# 7_dc_dc_3V3_3V3_Deployment_ANT.net
KiCad netlist of a schematic drawn in Altium Designer
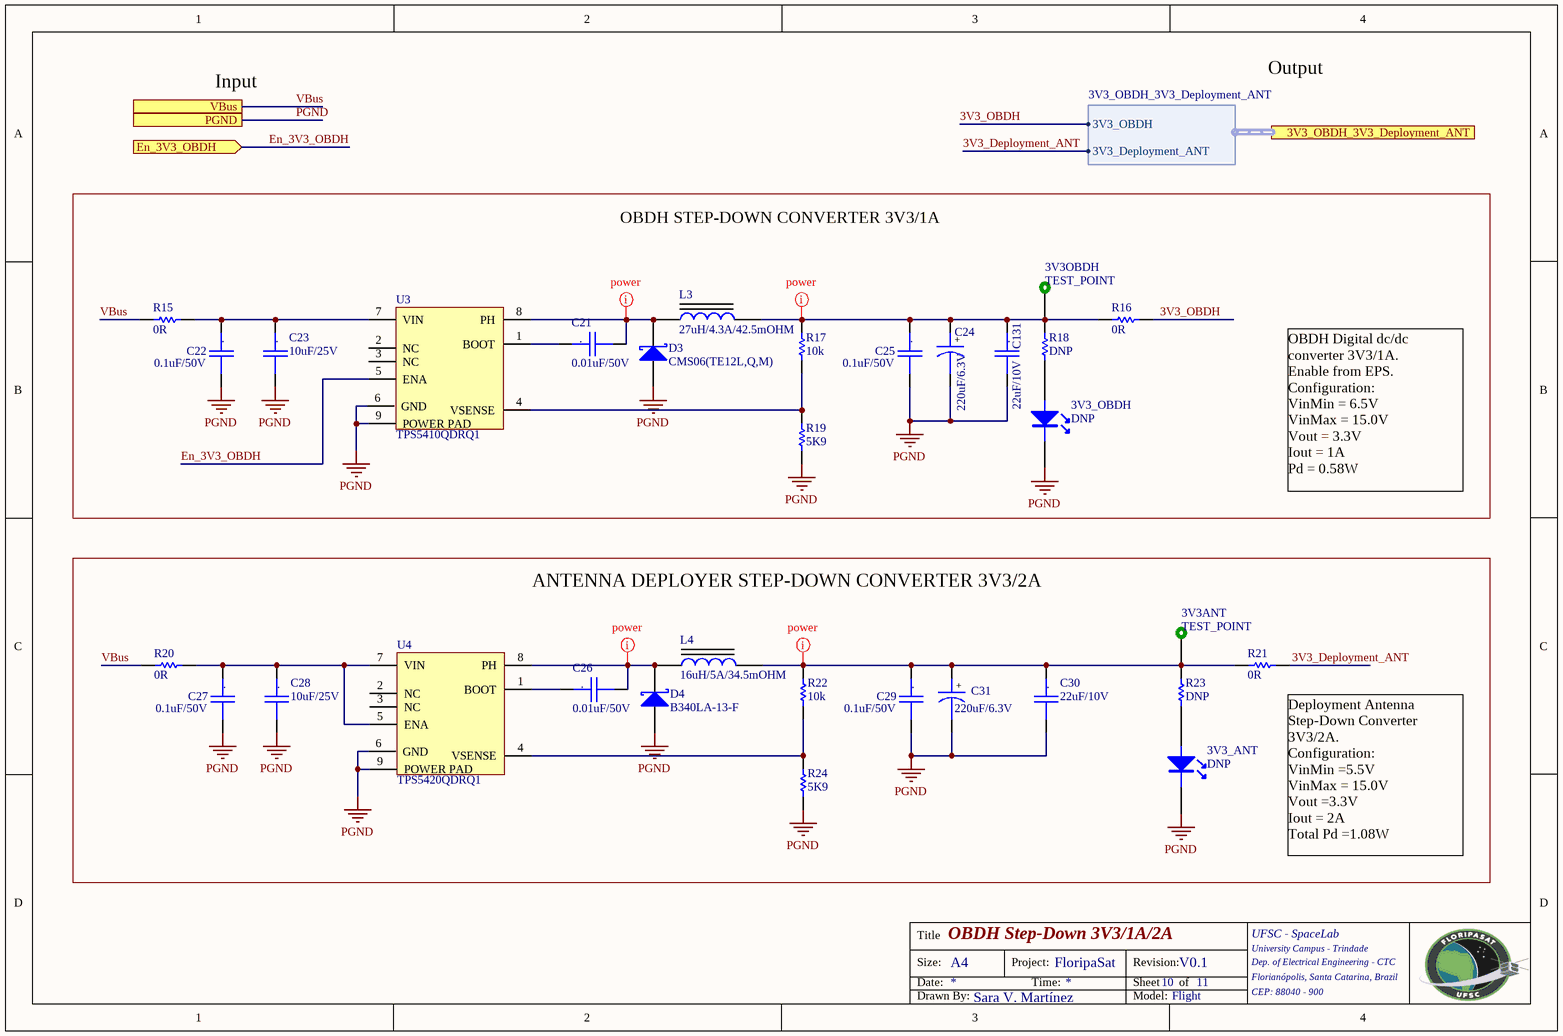
[diagram p0: 7_dc_dc_3V3_3V3_Deployment_ANT.SchDoc]

(export (version "E")
  (design (tool "Eeschema 10.0.6"))
  (components
    (comp (ref "3V3ANT")
      (value "TEST_POINT")
      (footprint "TEST_POINT")
      (description "Test point")
      (libsource (lib "Floripasat_lib") (part "TEST_POINT"))
    )
    (comp (ref "3V3OBDH")
      (value "TEST_POINT")
      (footprint "TEST_POINT")
      (description "Test point")
      (libsource (lib "Floripasat_lib") (part "TEST_POINT"))
    )
    (comp (ref "3V3_ANT")
      (value "DNP")
      (footprint "0603-LED")
      (description "SMD Green LED")
      (fields (field (name "PARTNUMBER") "150060VS75000"))
      (libsource (lib "FloripaSatSchlib") (part "LED/G_0603"))
    )
    (comp (ref "3V3_OBDH")
      (value "DNP")
      (footprint "0603-LED")
      (description "SMD Green LED")
      (fields (field (name "PARTNUMBER") "150060VS75000"))
      (libsource (lib "FloripaSatSchlib") (part "LED/G_0603"))
    )
    (comp (ref "C21")
      (value "0.01uF/50V")
      (footprint "CC0805")
      (description "CAP CER 0.01uF 50V 10% X7R 0805")
      (fields (field (name "PARTNUMBER") "08055C103KAT4A"))
      (libsource (lib "PCB_Project_FlightModel_EPS") (part "Cap_Cer_X7R_0.01uF_50V_0805"))
    )
    (comp (ref "C22")
      (value "0.1uF/50V")
      (footprint "CC0805")
      (description "CAP CER 0.1UF 50V 10% X7R 0805")
      (fields (field (name "PARTNUMBER") "CC0805KRX7R9BB104"))
      (libsource (lib "PCB_Project_FlightModel_EPS") (part "Cap_Cer_X7R_0.1uF_50V_0805"))
    )
    (comp (ref "C23")
      (value "10uF/25V")
      (footprint "CC1206")
      (description "CAP CER 10uF 25V 10% X7R 1206")
      (fields (field (name "PARTNUMBER") "GRM31CR71E106KA12L"))
      (libsource (lib "Floripasat_lib") (part "Cap_Cer_X7R_10uF_25V_1206"))
    )
    (comp (ref "C24")
      (value "220uF/6.3V")
      (footprint "FloripaSatPcbLib:cc1210")
      (description "CAP Tantalum 220uF 6.3V 20% 1210")
      (fields (field (name "PARTNUMBER") "6TPE220MAZB"))
      (libsource (lib "Floripasat_lib") (part "Cap_Tant_SMD_220uF_6.3V_1210"))
    )
    (comp (ref "C25")
      (value "0.1uF/50V")
      (footprint "CC0805")
      (description "CAP CER 0.1UF 50V 10% X7R 0805")
      (fields (field (name "PARTNUMBER") "CC0805KRX7R9BB104"))
      (libsource (lib "PCB_Project_FlightModel_EPS") (part "Cap_Cer_X7R_0.1uF_50V_0805"))
    )
    (comp (ref "C26")
      (value "0.01uF/50V")
      (footprint "CC0805")
      (description "CAP CER 0.01uF 50V 10% X7R 0805")
      (fields (field (name "PARTNUMBER") "08055C103KAT4A"))
      (libsource (lib "PCB_Project_FlightModel_EPS") (part "Cap_Cer_X7R_0.01uF_50V_0805"))
    )
    (comp (ref "C27")
      (value "0.1uF/50V")
      (footprint "CC0805")
      (description "CAP CER 0.1UF 50V 10% X7R 0805")
      (fields (field (name "PARTNUMBER") "CC0805KRX7R9BB104"))
      (libsource (lib "PCB_Project_FlightModel_EPS") (part "Cap_Cer_X7R_0.1uF_50V_0805"))
    )
    (comp (ref "C28")
      (value "10uF/25V")
      (footprint "CC1206")
      (description "CAP CER 10uF 25V 10% X7R 1206")
      (fields (field (name "PARTNUMBER") "GRM31CR71E106KA12L"))
      (libsource (lib "Floripasat_lib") (part "Cap_Cer_X7R_10uF_25V_1206"))
    )
    (comp (ref "C29")
      (value "0.1uF/50V")
      (footprint "CC0805")
      (description "CAP CER 0.1UF 50V 10% X7R 0805")
      (fields (field (name "PARTNUMBER") "CC0805KRX7R9BB104"))
      (libsource (lib "PCB_Project_FlightModel_EPS") (part "Cap_Cer_X7R_0.1uF_50V_0805"))
    )
    (comp (ref "C30")
      (value "22uF/10V")
      (footprint "CC1206")
      (description "CAP CER 22uF 10V 10% X7R 1206")
      (fields (field (name "PARTNUMBER") "GRM31CR71A226KE15L"))
      (libsource (lib "PCB_Project_FlightModel_EPS") (part "Cap_Cer_X7R_22uF_10V_1206"))
    )
    (comp (ref "C31")
      (value "220uF/6.3V")
      (footprint "FloripaSatPcbLib:cc1210")
      (description "CAP Tantalum 220uF 6.3V 20% 1210")
      (fields (field (name "PARTNUMBER") "6TPE220MAZB"))
      (libsource (lib "Floripasat_lib") (part "Cap_Tant_SMD_220uF_6.3V_1210"))
    )
    (comp (ref "C131")
      (value "22uF/10V")
      (footprint "CC1206")
      (description "CAP CER 22uF 10V 10% X7R 1206")
      (fields (field (name "PARTNUMBER") "GRM31CR71A226KE15L"))
      (libsource (lib "PCB_Project_FlightModel_EPS") (part "Cap_Cer_X7R_22uF_10V_1206"))
    )
    (comp (ref "D3")
      (value "CMS06(TE12L,Q,M)")
      (footprint "cms06")
      (description "DIODE SCHOTTKY 30V 2A   CMS06(TE12L,Q,M)")
      (libsource (lib "FloripaSatSchlib") (part "DIODE_SCHOTTKY_30V_2A_  CMS06(TE12L,Q,M)"))
    )
    (comp (ref "D4")
      (value "B340LA-13-F")
      (footprint "DO-214AC")
      (description "DIODE SCHOTTKY 40V 3A B340LA-13-F")
      (libsource (lib "FloripaSatSchlib") (part "DIODE_SCHOTTKY_40V_3A_B340LA-13-F"))
    )
    (comp (ref "L3")
      (value "27uH/4.3A/42.5mOHM")
      (footprint "IND_744325xxx")
      (description "INDUCTOR 27UH 4.3A SMD")
      (fields (field (name "PARTNUMBER") "7447798271"))
      (libsource (lib "FloripaSatSchlib") (part "IND_POWER_27uH_4.3A_42.5mR"))
    )
    (comp (ref "L4")
      (value "16uH/5A/34.5mOHM")
      (footprint "IND_744325xxx")
      (description "INDUCTOR 16UH 5A SMD")
      (fields (field (name "PARTNUMBER") "7443251600"))
      (libsource (lib "FloripaSatSchlib") (part "IND_POWER_16uH_5A_35.5mR"))
    )
    (comp (ref "R15")
      (value "0R")
      (footprint "1206")
      (description "RES 0.0 OHM 3/4W JUMP 1206")
      (fields (field (name "PARTNUMBER") "HCJ1206ZT0R00"))
      (libsource (lib "PCB_Project_FlightModel_EPS") (part "R0R_JUMPER_3/4W_1206"))
    )
    (comp (ref "R16")
      (value "0R")
      (footprint "1206")
      (description "RES 0.0 OHM 3/4W JUMP 1206")
      (fields (field (name "PARTNUMBER") "HCJ1206ZT0R00"))
      (libsource (lib "PCB_Project_FlightModel_EPS") (part "R0R_JUMPER_3/4W_1206"))
    )
    (comp (ref "R17")
      (value "10k")
      (footprint "0805")
      (description "RES 10K OHM 1/8W 1%  0805")
      (fields (field (name "PARTNUMBER") "CRCW080510K0FKEA"))
      (libsource (lib "FloripaSatSchlib") (part "R10k_1%_1/8W_0805"))
    )
    (comp (ref "R18")
      (value "DNP")
      (footprint "0603")
      (description "RES 1.0K OHM 1/8W 1% 0603")
      (fields (field (name "PARTNUMBER") "MCT06030C1001FP500"))
      (libsource (lib "FloripaSatSchlib") (part "R1.0k_1%_1/8W_0603"))
    )
    (comp (ref "R19")
      (value "5K9")
      (footprint "0805")
      (description "RES 5K9 OHM 1/8W 1% 0805")
      (fields (field (name "PARTNUMBER") "71-CRCW0805-5.9K-E3"))
      (libsource (lib "FloripaSatSchlib") (part "R5.9K_1%_1/8W_0805"))
    )
    (comp (ref "R20")
      (value "0R")
      (footprint "1206")
      (description "RES 0.0 OHM 3/4W JUMP 1206")
      (fields (field (name "PARTNUMBER") "HCJ1206ZT0R00"))
      (libsource (lib "PCB_Project_FlightModel_EPS") (part "R0R_JUMPER_3/4W_1206"))
    )
    (comp (ref "R21")
      (value "0R")
      (footprint "1206")
      (description "RES 0.0 OHM 3/4W JUMP 1206")
      (fields (field (name "PARTNUMBER") "HCJ1206ZT0R00"))
      (libsource (lib "PCB_Project_FlightModel_EPS") (part "R0R_JUMPER_3/4W_1206"))
    )
    (comp (ref "R22")
      (value "10k")
      (footprint "0805")
      (description "RES 10K OHM 1/8W 1%  0805")
      (fields (field (name "PARTNUMBER") "CRCW080510K0FKEA"))
      (libsource (lib "FloripaSatSchlib") (part "R10k_1%_1/8W_0805"))
    )
    (comp (ref "R23")
      (value "DNP")
      (footprint "0603")
      (description "RES 1.0K OHM 1/8W 1% 0603")
      (fields (field (name "PARTNUMBER") "MCT06030C1001FP500"))
      (libsource (lib "FloripaSatSchlib") (part "R1.0k_1%_1/8W_0603"))
    )
    (comp (ref "R24")
      (value "5K9")
      (footprint "0805")
      (description "RES 5K9 OHM 1/8W 1% 0805")
      (fields (field (name "PARTNUMBER") "71-CRCW0805-5.9K-E3"))
      (libsource (lib "FloripaSatSchlib") (part "R5.9K_1%_1/8W_0805"))
    )
    (comp (ref "U3")
      (value "TPS5410QDRQ1")
      (footprint "SO8 Power PAD")
      (libsource (lib "FloripaSatSchlib") (part "TPS5410QDRQ1"))
    )
    (comp (ref "U4")
      (value "TPS5420QDRQ1")
      (footprint "SO8 Power PAD")
      (libsource (lib "FloripaSatSchlib") (part "TPS5420QDRQ1"))
    )
  )
  (nets
    (net (code "2") (name "/3V3_Deployment_ANT") (class "Default")
      (node (ref "R21") (pin "1") (pinfunction "1_1") (pintype "passive"))
    )
    (net (code "3") (name "/3V3_OBDH") (class "Default")
      (node (ref "R16") (pin "1") (pinfunction "1_1") (pintype "passive"))
    )
    (net (code "4") (name "/En_3V3_OBDH") (class "Default")
      (node (ref "U3") (pin "5") (pinfunction "ENA_5") (pintype "passive"))
    )
    (net (code "5") (name "/VBus") (class "Default")
      (node (ref "R15") (pin "2") (pinfunction "2_2") (pintype "passive"))
      (node (ref "R20") (pin "2") (pinfunction "2_2") (pintype "passive"))
    )
    (net (code "7") (name "Net-(3V3ANT-Pad1)") (class "Default")
      (node (ref "3V3ANT") (pin "1") (pinfunction "1_1") (pintype "passive"))
      (node (ref "C29") (pin "1") (pinfunction "1_1") (pintype "passive"))
      (node (ref "C30") (pin "1") (pinfunction "1_1") (pintype "passive"))
      (node (ref "C31") (pin "1") (pinfunction "1_1") (pintype "passive"))
      (node (ref "L4") (pin "2") (pinfunction "2_2") (pintype "passive"))
      (node (ref "R21") (pin "2") (pinfunction "2_2") (pintype "passive"))
      (node (ref "R22") (pin "2") (pinfunction "2_2") (pintype "passive"))
      (node (ref "R23") (pin "1") (pinfunction "1_1") (pintype "passive"))
    )
    (net (code "8") (name "Net-(3V3OBDH-Pad1)") (class "Default")
      (node (ref "3V3OBDH") (pin "1") (pinfunction "1_1") (pintype "passive"))
      (node (ref "C131") (pin "1") (pinfunction "1_1") (pintype "passive"))
      (node (ref "C24") (pin "1") (pinfunction "1_1") (pintype "passive"))
      (node (ref "C25") (pin "1") (pinfunction "1_1") (pintype "passive"))
      (node (ref "L3") (pin "2") (pinfunction "2_2") (pintype "passive"))
      (node (ref "R16") (pin "2") (pinfunction "2_2") (pintype "passive"))
      (node (ref "R17") (pin "2") (pinfunction "2_2") (pintype "passive"))
      (node (ref "R18") (pin "1") (pinfunction "1_1") (pintype "passive"))
    )
    (net (code "9") (name "Net-(3V3_ANT-A)") (class "Default")
      (node (ref "3V3_ANT") (pin "1") (pinfunction "A_1") (pintype "passive"))
      (node (ref "R23") (pin "2") (pinfunction "2_2") (pintype "passive"))
    )
    (net (code "10") (name "Net-(3V3_OBDH-A)") (class "Default")
      (node (ref "3V3_OBDH") (pin "1") (pinfunction "A_1") (pintype "passive"))
      (node (ref "R18") (pin "2") (pinfunction "2_2") (pintype "passive"))
    )
    (net (code "11") (name "Net-(D3-K)") (class "Default")
      (node (ref "C21") (pin "2") (pinfunction "2_2") (pintype "passive"))
      (node (ref "D3") (pin "1") (pinfunction "K_1") (pintype "passive"))
      (node (ref "L3") (pin "1") (pinfunction "1_1") (pintype "passive"))
      (node (ref "U3") (pin "8") (pinfunction "PH_8") (pintype "passive"))
    )
    (net (code "12") (name "Net-(D4-K)") (class "Default")
      (node (ref "C26") (pin "2") (pinfunction "2_2") (pintype "passive"))
      (node (ref "D4") (pin "1") (pinfunction "K_1") (pintype "passive"))
      (node (ref "L4") (pin "1") (pinfunction "1_1") (pintype "passive"))
      (node (ref "U4") (pin "8") (pinfunction "PH_8") (pintype "passive"))
    )
    (net (code "13") (name "Net-(U3-BOOT)") (class "Default")
      (node (ref "C21") (pin "1") (pinfunction "1_1") (pintype "passive"))
      (node (ref "U3") (pin "1") (pinfunction "BOOT_1") (pintype "passive"))
    )
    (net (code "14") (name "Net-(U3-VIN)") (class "Default")
      (node (ref "C22") (pin "1") (pinfunction "1_1") (pintype "passive"))
      (node (ref "C23") (pin "1") (pinfunction "1_1") (pintype "passive"))
      (node (ref "R15") (pin "1") (pinfunction "1_1") (pintype "passive"))
      (node (ref "U3") (pin "7") (pinfunction "VIN_7") (pintype "passive"))
    )
    (net (code "15") (name "Net-(U3-VSENSE)") (class "Default")
      (node (ref "R17") (pin "1") (pinfunction "1_1") (pintype "passive"))
      (node (ref "R19") (pin "2") (pinfunction "2_2") (pintype "passive"))
      (node (ref "U3") (pin "4") (pinfunction "VSENSE_4") (pintype "passive"))
    )
    (net (code "16") (name "Net-(U4-BOOT)") (class "Default")
      (node (ref "C26") (pin "1") (pinfunction "1_1") (pintype "passive"))
      (node (ref "U4") (pin "1") (pinfunction "BOOT_1") (pintype "passive"))
    )
    (net (code "17") (name "Net-(U4-ENA)") (class "Default")
      (node (ref "C27") (pin "1") (pinfunction "1_1") (pintype "passive"))
      (node (ref "C28") (pin "1") (pinfunction "1_1") (pintype "passive"))
      (node (ref "R20") (pin "1") (pinfunction "1_1") (pintype "passive"))
      (node (ref "U4") (pin "5") (pinfunction "ENA_5") (pintype "passive"))
      (node (ref "U4") (pin "7") (pinfunction "VIN_7") (pintype "passive"))
    )
    (net (code "18") (name "Net-(U4-VSENSE)") (class "Default")
      (node (ref "R22") (pin "1") (pinfunction "1_1") (pintype "passive"))
      (node (ref "R24") (pin "2") (pinfunction "2_2") (pintype "passive"))
      (node (ref "U4") (pin "4") (pinfunction "VSENSE_4") (pintype "passive"))
    )
    (net (code "19") (name "PGND") (class "Default")
      (node (ref "3V3_ANT") (pin "2") (pinfunction "K_2") (pintype "passive"))
      (node (ref "3V3_OBDH") (pin "2") (pinfunction "K_2") (pintype "passive"))
      (node (ref "C131") (pin "2") (pinfunction "2_2") (pintype "passive"))
      (node (ref "C22") (pin "2") (pinfunction "2_2") (pintype "passive"))
      (node (ref "C23") (pin "2") (pinfunction "2_2") (pintype "passive"))
      (node (ref "C24") (pin "2") (pinfunction "2_2") (pintype "passive"))
      (node (ref "C25") (pin "2") (pinfunction "2_2") (pintype "passive"))
      (node (ref "C27") (pin "2") (pinfunction "2_2") (pintype "passive"))
      (node (ref "C28") (pin "2") (pinfunction "2_2") (pintype "passive"))
      (node (ref "C29") (pin "2") (pinfunction "2_2") (pintype "passive"))
      (node (ref "C30") (pin "2") (pinfunction "2_2") (pintype "passive"))
      (node (ref "C31") (pin "2") (pinfunction "2_2") (pintype "passive"))
      (node (ref "D3") (pin "2") (pinfunction "A_2") (pintype "passive"))
      (node (ref "D4") (pin "2") (pinfunction "A_2") (pintype "passive"))
      (node (ref "R19") (pin "1") (pinfunction "1_1") (pintype "passive"))
      (node (ref "R24") (pin "1") (pinfunction "1_1") (pintype "passive"))
      (node (ref "U3") (pin "6") (pinfunction "GND_6") (pintype "passive"))
      (node (ref "U3") (pin "9") (pinfunction "POWER_PAD_9") (pintype "passive"))
      (node (ref "U4") (pin "6") (pinfunction "GND_6") (pintype "passive"))
      (node (ref "U4") (pin "9") (pinfunction "POWER_PAD_9") (pintype "passive"))
    )
    (net (code "20") (name "unconnected-(U3-NC-Pad2)") (class "Default")
      (node (ref "U3") (pin "2") (pinfunction "NC_2") (pintype "passive"))
    )
    (net (code "21") (name "unconnected-(U3-NC-Pad3)") (class "Default")
      (node (ref "U3") (pin "3") (pinfunction "NC_3") (pintype "passive"))
    )
    (net (code "22") (name "unconnected-(U4-NC-Pad2)") (class "Default")
      (node (ref "U4") (pin "2") (pinfunction "NC_2") (pintype "passive"))
    )
    (net (code "23") (name "unconnected-(U4-NC-Pad3)") (class "Default")
      (node (ref "U4") (pin "3") (pinfunction "NC_3") (pintype "passive"))
    )
  )
)
